# scenes_main.net
KiCad netlist of a schematic drawn in EAGLE
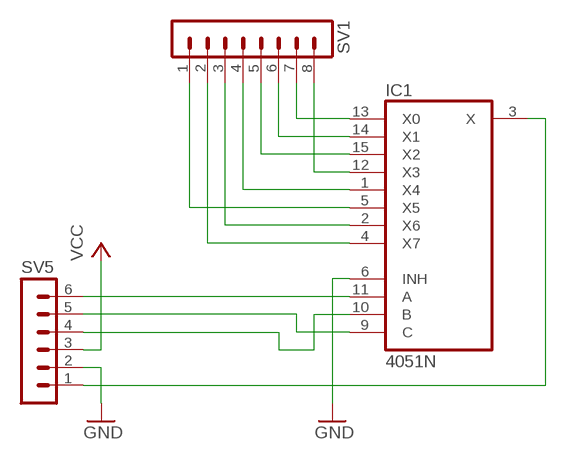
[diagram p0: schematic, sheet 1]

(export (version "E")
  (design (tool "Eeschema 10.0.6"))
  (components
    (comp (ref "IC1")
      (value "4051N")
      (footprint "eagle-import:DIL16")
      (libsource (lib "eagle-import") (part "4051N"))
    )
    (comp (ref "SV1")
      (value "MA08-1")
      (footprint "eagle-import:MA08-1")
      (libsource (lib "eagle-import") (part "MA08-1"))
    )
    (comp (ref "SV5")
      (value "MA06-1")
      (footprint "eagle-import:MA06-1")
      (libsource (lib "eagle-import") (part "MA06-1"))
    )
  )
  (nets
    (net (code "1") (name "GND") (class "Default")
      (node (ref "IC1") (pin "6") (pinfunction "INH_6") (pintype "input"))
      (node (ref "SV5") (pin "2") (pinfunction "2_2") (pintype "passive"))
    )
    (net (code "2") (name "Net-(IC1A-A)") (class "Default")
      (node (ref "IC1") (pin "11") (pinfunction "A_11") (pintype "input"))
      (node (ref "SV5") (pin "6") (pinfunction "6_6") (pintype "passive"))
    )
    (net (code "3") (name "Net-(IC1A-B)") (class "Default")
      (node (ref "IC1") (pin "10") (pinfunction "B_10") (pintype "input"))
      (node (ref "SV5") (pin "4") (pinfunction "4_4") (pintype "passive"))
    )
    (net (code "4") (name "Net-(IC1A-C)") (class "Default")
      (node (ref "IC1") (pin "9") (pinfunction "C_9") (pintype "input"))
      (node (ref "SV5") (pin "5") (pinfunction "5_5") (pintype "passive"))
    )
    (net (code "5") (name "Net-(IC1A-X)") (class "Default")
      (node (ref "IC1") (pin "3") (pinfunction "X_3") (pintype "bidirectional"))
      (node (ref "SV5") (pin "1") (pinfunction "1_1") (pintype "passive"))
    )
    (net (code "6") (name "Net-(IC1A-X0)") (class "Default")
      (node (ref "IC1") (pin "13") (pinfunction "X0_13") (pintype "bidirectional"))
      (node (ref "SV1") (pin "7") (pinfunction "7_7") (pintype "passive"))
    )
    (net (code "7") (name "Net-(IC1A-X1)") (class "Default")
      (node (ref "IC1") (pin "14") (pinfunction "X1_14") (pintype "bidirectional"))
      (node (ref "SV1") (pin "6") (pinfunction "6_6") (pintype "passive"))
    )
    (net (code "8") (name "Net-(IC1A-X2)") (class "Default")
      (node (ref "IC1") (pin "15") (pinfunction "X2_15") (pintype "bidirectional"))
      (node (ref "SV1") (pin "5") (pinfunction "5_5") (pintype "passive"))
    )
    (net (code "9") (name "Net-(IC1A-X3)") (class "Default")
      (node (ref "IC1") (pin "12") (pinfunction "X3_12") (pintype "bidirectional"))
      (node (ref "SV1") (pin "8") (pinfunction "8_8") (pintype "passive"))
    )
    (net (code "10") (name "Net-(IC1A-X4)") (class "Default")
      (node (ref "IC1") (pin "1") (pinfunction "X4_1") (pintype "bidirectional"))
      (node (ref "SV1") (pin "4") (pinfunction "4_4") (pintype "passive"))
    )
    (net (code "11") (name "Net-(IC1A-X5)") (class "Default")
      (node (ref "IC1") (pin "5") (pinfunction "X5_5") (pintype "bidirectional"))
      (node (ref "SV1") (pin "1") (pinfunction "1_1") (pintype "passive"))
    )
    (net (code "12") (name "Net-(IC1A-X6)") (class "Default")
      (node (ref "IC1") (pin "2") (pinfunction "X6_2") (pintype "bidirectional"))
      (node (ref "SV1") (pin "3") (pinfunction "3_3") (pintype "passive"))
    )
    (net (code "13") (name "Net-(IC1A-X7)") (class "Default")
      (node (ref "IC1") (pin "4") (pinfunction "X7_4") (pintype "bidirectional"))
      (node (ref "SV1") (pin "2") (pinfunction "2_2") (pintype "passive"))
    )
    (net (code "14") (name "VCC") (class "Default")
      (node (ref "SV5") (pin "3") (pinfunction "3_3") (pintype "passive"))
    )
  )
)
